# ds_shield.net
KiCad netlist of a schematic drawn in EAGLE
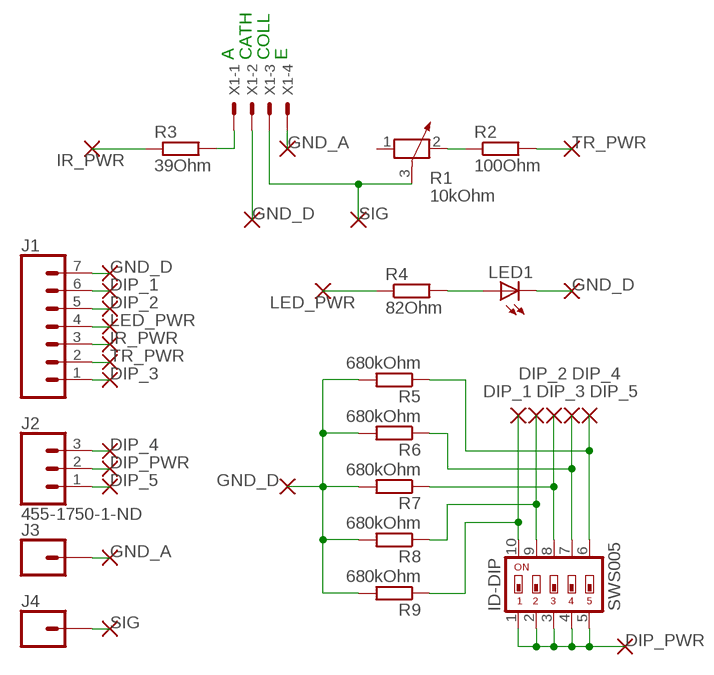
[diagram p0: schematic, sheet 1]

(export (version "E")
  (design (tool "Eeschema 10.0.6"))
  (components
    (comp (ref "ID-DIP")
      (value "SWS005")
      (footprint "eagle-import:SMS-005")
      (libsource (lib "eagle-import") (part "SWS005"))
    )
    (comp (ref "J1")
      (value "CONN_07")
      (footprint "eagle-import:1X07")
      (libsource (lib "eagle-import") (part "CONN_07"))
    )
    (comp (ref "J2")
      (value "455-1750-1-ND")
      (footprint "eagle-import:1X03")
      (libsource (lib "eagle-import") (part "CONN_03"))
    )
    (comp (ref "J3")
      (value "CONN_01")
      (footprint "eagle-import:1X01")
      (libsource (lib "eagle-import") (part "CONN_01"))
    )
    (comp (ref "J4")
      (value "CONN_01")
      (footprint "eagle-import:1X01")
      (libsource (lib "eagle-import") (part "CONN_01"))
    )
    (comp (ref "LED1")
      (value "LED3MM")
      (footprint "eagle-import:LED3MM")
      (libsource (lib "eagle-import") (part "LED3MM"))
    )
    (comp (ref "R1")
      (value "10kOhm")
      (footprint "eagle-import:PT-10")
      (libsource (lib "eagle-import") (part "POTENTIOMETER_PT-10"))
    )
    (comp (ref "R2")
      (value "100Ohm")
      (footprint "eagle-import:0204_5")
      (libsource (lib "eagle-import") (part "R-EU_0204/5"))
    )
    (comp (ref "R3")
      (value "39Ohm")
      (footprint "eagle-import:0204_5")
      (libsource (lib "eagle-import") (part "R-EU_0204/5"))
    )
    (comp (ref "R4")
      (value "82Ohm")
      (footprint "eagle-import:0204_5")
      (libsource (lib "eagle-import") (part "R-EU_0204/5"))
    )
    (comp (ref "R5")
      (value "680kOhm")
      (footprint "eagle-import:0204_5")
      (libsource (lib "eagle-import") (part "resistor_348_R-EU_0204/5"))
    )
    (comp (ref "R6")
      (value "680kOhm")
      (footprint "eagle-import:0204_5")
      (libsource (lib "eagle-import") (part "resistor_348_R-EU_0204/5"))
    )
    (comp (ref "R7")
      (value "680kOhm")
      (footprint "eagle-import:0204_5")
      (libsource (lib "eagle-import") (part "resistor_348_R-EU_0204/5"))
    )
    (comp (ref "R8")
      (value "680kOhm")
      (footprint "eagle-import:0204_5")
      (libsource (lib "eagle-import") (part "resistor_348_R-EU_0204/5"))
    )
    (comp (ref "R9")
      (value "680kOhm")
      (footprint "eagle-import:0204_5")
      (libsource (lib "eagle-import") (part "resistor_348_R-EU_0204/5"))
    )
    (comp (ref "X1")
      (value "KK-156-4")
      (footprint "eagle-import:KK-156-4")
      (fields (field (name "MF") "MOLEX"))
      (libsource (lib "eagle-import") (part "KK-156-4"))
    )
  )
  (nets
    (net (code "1") (name "/DIP_1") (class "Default")
      (node (ref "ID-DIP") (pin "10") (pinfunction "10_10") (pintype "passive"))
      (node (ref "J1") (pin "6") (pinfunction "6_6") (pintype "passive"))
      (node (ref "R9") (pin "1") (pinfunction "1_1") (pintype "passive"))
    )
    (net (code "2") (name "/DIP_2") (class "Default")
      (node (ref "ID-DIP") (pin "9") (pinfunction "9_9") (pintype "passive"))
      (node (ref "J1") (pin "5") (pinfunction "5_5") (pintype "passive"))
      (node (ref "R8") (pin "1") (pinfunction "1_1") (pintype "passive"))
    )
    (net (code "3") (name "/DIP_3") (class "Default")
      (node (ref "ID-DIP") (pin "8") (pinfunction "8_8") (pintype "passive"))
      (node (ref "J1") (pin "1") (pinfunction "1_1") (pintype "passive"))
      (node (ref "R7") (pin "1") (pinfunction "1_1") (pintype "passive"))
    )
    (net (code "4") (name "/DIP_4") (class "Default")
      (node (ref "ID-DIP") (pin "7") (pinfunction "7_7") (pintype "passive"))
      (node (ref "J2") (pin "3") (pinfunction "3_3") (pintype "passive"))
      (node (ref "R6") (pin "1") (pinfunction "1_1") (pintype "passive"))
    )
    (net (code "5") (name "/DIP_5") (class "Default")
      (node (ref "ID-DIP") (pin "6") (pinfunction "6_6") (pintype "passive"))
      (node (ref "J2") (pin "1") (pinfunction "1_1") (pintype "passive"))
      (node (ref "R5") (pin "1") (pinfunction "1_1") (pintype "passive"))
    )
    (net (code "6") (name "/DIP_PWR") (class "Default")
      (node (ref "ID-DIP") (pin "1") (pinfunction "1_1") (pintype "passive"))
      (node (ref "ID-DIP") (pin "2") (pinfunction "2_2") (pintype "passive"))
      (node (ref "ID-DIP") (pin "3") (pinfunction "3_3") (pintype "passive"))
      (node (ref "ID-DIP") (pin "4") (pinfunction "4_4") (pintype "passive"))
      (node (ref "ID-DIP") (pin "5") (pinfunction "5_5") (pintype "passive"))
      (node (ref "J2") (pin "2") (pinfunction "2_2") (pintype "passive"))
    )
    (net (code "7") (name "/GND_A") (class "Default")
      (node (ref "J3") (pin "1") (pinfunction "1_1") (pintype "passive"))
      (node (ref "X1") (pin "4") (pinfunction "S_4") (pintype "passive"))
    )
    (net (code "8") (name "/GND_D") (class "Default")
      (node (ref "J1") (pin "7") (pinfunction "7_7") (pintype "passive"))
      (node (ref "LED1") (pin "K") (pinfunction "C_K") (pintype "passive"))
      (node (ref "R5") (pin "2") (pinfunction "2_2") (pintype "passive"))
      (node (ref "R6") (pin "2") (pinfunction "2_2") (pintype "passive"))
      (node (ref "R7") (pin "2") (pinfunction "2_2") (pintype "passive"))
      (node (ref "R8") (pin "2") (pinfunction "2_2") (pintype "passive"))
      (node (ref "R9") (pin "2") (pinfunction "2_2") (pintype "passive"))
      (node (ref "X1") (pin "2") (pinfunction "S_2") (pintype "passive"))
    )
    (net (code "9") (name "/IR_PWR") (class "Default")
      (node (ref "J1") (pin "3") (pinfunction "3_3") (pintype "passive"))
      (node (ref "R3") (pin "1") (pinfunction "1_1") (pintype "passive"))
    )
    (net (code "10") (name "/LED_PWR") (class "Default")
      (node (ref "J1") (pin "4") (pinfunction "4_4") (pintype "passive"))
      (node (ref "R4") (pin "1") (pinfunction "1_1") (pintype "passive"))
    )
    (net (code "11") (name "/SIG") (class "Default")
      (node (ref "J4") (pin "1") (pinfunction "1_1") (pintype "passive"))
      (node (ref "R1") (pin "3") (pinfunction "3_3") (pintype "passive"))
      (node (ref "X1") (pin "3") (pinfunction "S_3") (pintype "passive"))
    )
    (net (code "12") (name "/TR_PWR") (class "Default")
      (node (ref "J1") (pin "2") (pinfunction "2_2") (pintype "passive"))
      (node (ref "R2") (pin "2") (pinfunction "2_2") (pintype "passive"))
    )
    (net (code "13") (name "Net-(LED1-PadA)") (class "Default")
      (node (ref "LED1") (pin "A") (pinfunction "A_A") (pintype "passive"))
      (node (ref "R4") (pin "2") (pinfunction "2_2") (pintype "passive"))
    )
    (net (code "14") (name "Net-(R1-Pad2)") (class "Default")
      (node (ref "R1") (pin "2") (pinfunction "2_2") (pintype "passive"))
      (node (ref "R2") (pin "1") (pinfunction "1_1") (pintype "passive"))
    )
    (net (code "15") (name "Net-(X1A-S)") (class "Default")
      (node (ref "R3") (pin "2") (pinfunction "2_2") (pintype "passive"))
      (node (ref "X1") (pin "1") (pinfunction "S_1") (pintype "passive"))
    )
    (net (code "16") (name "unconnected-(R1-Pad1)") (class "Default")
      (node (ref "R1") (pin "1") (pinfunction "1_1") (pintype "passive"))
    )
  )
)
